# Load_Bank_Mosfet_Control_Board.net
KiCad netlist of a schematic drawn in EAGLE
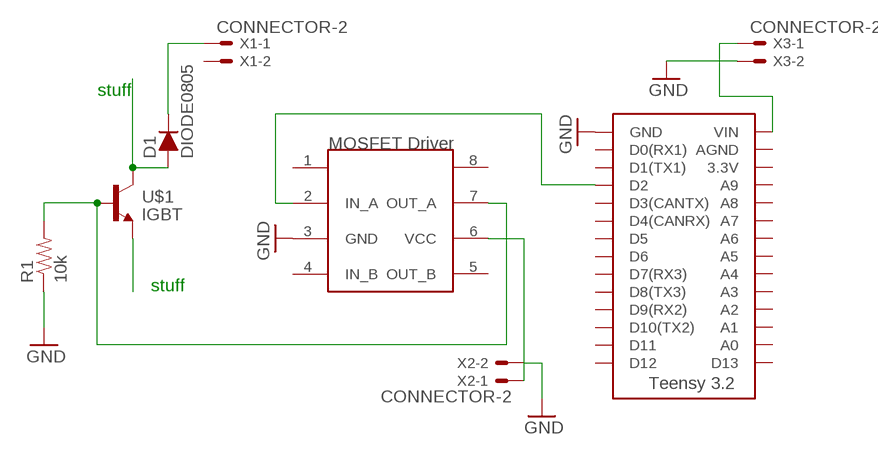
[diagram p0: schematic, sheet 1]

(export (version "E")
  (design (tool "Eeschema 10.0.6"))
  (components
    (comp (ref "D1")
      (value "DIODE0805")
      (footprint "eagle-import:0805_D")
      (libsource (lib "eagle-import") (part "DIODE0805"))
    )
    (comp (ref "R1")
      (value "10k")
      (footprint "eagle-import:0402-RES")
      (libsource (lib "eagle-import") (part "RESISTOR0402"))
    )
    (comp (ref "U$1")
      (value "IGBT")
      (footprint "eagle-import:IGBT")
      (libsource (lib "eagle-import") (part "IGBT"))
    )
    (comp (ref "U$2")
      (value "MC34152")
      (footprint "eagle-import:SOIC-08")
      (libsource (lib "eagle-import") (part "MC34152"))
    )
    (comp (ref "U$3")
      (value "TEENSY_3.2_SIMPLE")
      (footprint "eagle-import:TEENSY_3.2_SIMPLE")
      (libsource (lib "eagle-import") (part "TEENSY_3.2_SIMPLE"))
    )
    (comp (ref "X1")
      (value "CONNECTOR-2")
      (footprint "eagle-import:MINIFIT_5566-2")
      (libsource (lib "eagle-import") (part "CONNECTOR-2"))
    )
    (comp (ref "X2")
      (value "CONNECTOR-2")
      (footprint "eagle-import:MINIFIT_5566-2")
      (libsource (lib "eagle-import") (part "CONNECTOR-2"))
    )
    (comp (ref "X3")
      (value "CONNECTOR-2")
      (footprint "eagle-import:MINIFIT_5566-2")
      (libsource (lib "eagle-import") (part "CONNECTOR-2"))
    )
  )
  (nets
    (net (code "1") (name "GND") (class "Default")
      (node (ref "R1") (pin "1") (pinfunction "1_1") (pintype "passive"))
      (node (ref "U$2") (pin "3") (pinfunction "GND_3") (pintype "power_in"))
      (node (ref "U$3") (pin "GND") (pinfunction "GND_GND") (pintype "bidirectional"))
      (node (ref "X2") (pin "2") (pinfunction "S_2") (pintype "passive"))
      (node (ref "X3") (pin "2") (pinfunction "S_2") (pintype "passive"))
    )
    (net (code "2") (name "Net-(U$1-BASE)") (class "Default")
      (node (ref "R1") (pin "2") (pinfunction "2_2") (pintype "passive"))
      (node (ref "U$1") (pin "P$3") (pinfunction "BASE_P$3") (pintype "passive"))
      (node (ref "U$2") (pin "7") (pinfunction "OUT_A_7") (pintype "output"))
    )
    (net (code "3") (name "Net-(U$1-COLLECTOR)") (class "Default")
      (node (ref "D1") (pin "A") (pinfunction "A_A") (pintype "passive"))
      (node (ref "U$1") (pin "P$2") (pinfunction "COLLECTOR_P$2") (pintype "passive"))
    )
    (net (code "4") (name "Net-(U$1-EMITTER-PadP$1)") (class "Default")
      (node (ref "U$1") (pin "P$1") (pinfunction "EMITTER_P$1") (pintype "passive"))
      (node (ref "U$1") (pin "P$4") (pinfunction "EMITTER_P$4") (pintype "passive"))
    )
    (net (code "5") (name "Net-(U$2-IN_A)") (class "Default")
      (node (ref "U$2") (pin "2") (pinfunction "IN_A_2") (pintype "input"))
      (node (ref "U$3") (pin "D2") (pinfunction "D2_D2") (pintype "bidirectional"))
    )
    (net (code "6") (name "Net-(U$2-VCC)") (class "Default")
      (node (ref "U$2") (pin "6") (pinfunction "VCC_6") (pintype "power_in"))
      (node (ref "X2") (pin "1") (pinfunction "S_1") (pintype "passive"))
    )
    (net (code "7") (name "Net-(X1A-S)") (class "Default")
      (node (ref "D1") (pin "C") (pinfunction "C_C") (pintype "passive"))
      (node (ref "X1") (pin "1") (pinfunction "S_1") (pintype "passive"))
    )
    (net (code "8") (name "Net-(X3A-S)") (class "Default")
      (node (ref "U$3") (pin "VIN") (pinfunction "VIN_VIN") (pintype "bidirectional"))
      (node (ref "X3") (pin "1") (pinfunction "S_1") (pintype "passive"))
    )
    (net (code "9") (name "unconnected-(U$2-IN_B-Pad4)") (class "Default")
      (node (ref "U$2") (pin "4") (pinfunction "IN_B_4") (pintype "bidirectional"))
    )
    (net (code "10") (name "unconnected-(U$2-OUT_B-Pad5)") (class "Default")
      (node (ref "U$2") (pin "5") (pinfunction "OUT_B_5") (pintype "output"))
    )
    (net (code "11") (name "unconnected-(U$2-P$1-Pad1)") (class "Default")
      (node (ref "U$2") (pin "1") (pinfunction "P$1_1") (pintype "tri_state"))
    )
    (net (code "12") (name "unconnected-(U$2-P$5-Pad8)") (class "Default")
      (node (ref "U$2") (pin "8") (pinfunction "P$5_8") (pintype "tri_state"))
    )
    (net (code "13") (name "unconnected-(U$3-Pad3.3V)") (class "Default")
      (node (ref "U$3") (pin "3.3V") (pinfunction "3.3V_3.3V") (pintype "bidirectional"))
    )
    (net (code "14") (name "unconnected-(U$3-PadA0)") (class "Default")
      (node (ref "U$3") (pin "A0") (pinfunction "A0_A0") (pintype "bidirectional"))
    )
    (net (code "15") (name "unconnected-(U$3-PadA1)") (class "Default")
      (node (ref "U$3") (pin "A1") (pinfunction "A1_A1") (pintype "bidirectional"))
    )
    (net (code "16") (name "unconnected-(U$3-PadA2)") (class "Default")
      (node (ref "U$3") (pin "A2") (pinfunction "A2_A2") (pintype "bidirectional"))
    )
    (net (code "17") (name "unconnected-(U$3-PadA3)") (class "Default")
      (node (ref "U$3") (pin "A3") (pinfunction "A3_A3") (pintype "bidirectional"))
    )
    (net (code "18") (name "unconnected-(U$3-PadA4)") (class "Default")
      (node (ref "U$3") (pin "A4") (pinfunction "A4_A4") (pintype "bidirectional"))
    )
    (net (code "19") (name "unconnected-(U$3-PadA5)") (class "Default")
      (node (ref "U$3") (pin "A5") (pinfunction "A5_A5") (pintype "bidirectional"))
    )
    (net (code "20") (name "unconnected-(U$3-PadA6)") (class "Default")
      (node (ref "U$3") (pin "A6") (pinfunction "A6_A6") (pintype "bidirectional"))
    )
    (net (code "21") (name "unconnected-(U$3-PadA7)") (class "Default")
      (node (ref "U$3") (pin "A7") (pinfunction "A7_A7") (pintype "bidirectional"))
    )
    (net (code "22") (name "unconnected-(U$3-PadA8)") (class "Default")
      (node (ref "U$3") (pin "A8") (pinfunction "A8_A8") (pintype "bidirectional"))
    )
    (net (code "23") (name "unconnected-(U$3-PadA9)") (class "Default")
      (node (ref "U$3") (pin "A9") (pinfunction "A9_A9") (pintype "bidirectional"))
    )
    (net (code "24") (name "unconnected-(U$3-PadAGND)") (class "Default")
      (node (ref "U$3") (pin "AGND") (pinfunction "AGND_AGND") (pintype "bidirectional"))
    )
    (net (code "25") (name "unconnected-(U$3-PadD0(RX1))") (class "Default")
      (node (ref "U$3") (pin "D0(RX1)") (pinfunction "D0(RX1)_D0(RX1)") (pintype "bidirectional"))
    )
    (net (code "26") (name "unconnected-(U$3-PadD1(TX1))") (class "Default")
      (node (ref "U$3") (pin "D1(TX1)") (pinfunction "D1(TX1)_D1(TX1)") (pintype "bidirectional"))
    )
    (net (code "27") (name "unconnected-(U$3-PadD3(CANTX))") (class "Default")
      (node (ref "U$3") (pin "D3(CANTX)") (pinfunction "D3(CANTX)_D3(CANTX)") (pintype "bidirectional"))
    )
    (net (code "28") (name "unconnected-(U$3-PadD4(CANRX))") (class "Default")
      (node (ref "U$3") (pin "D4(CANRX)") (pinfunction "D4(CANRX)_D4(CANRX)") (pintype "bidirectional"))
    )
    (net (code "29") (name "unconnected-(U$3-PadD5)") (class "Default")
      (node (ref "U$3") (pin "D5") (pinfunction "D5_D5") (pintype "bidirectional"))
    )
    (net (code "30") (name "unconnected-(U$3-PadD6)") (class "Default")
      (node (ref "U$3") (pin "D6") (pinfunction "D6_D6") (pintype "bidirectional"))
    )
    (net (code "31") (name "unconnected-(U$3-PadD7(RX3))") (class "Default")
      (node (ref "U$3") (pin "D7(RX3)") (pinfunction "D7(RX3)_D7(RX3)") (pintype "bidirectional"))
    )
    (net (code "32") (name "unconnected-(U$3-PadD8(TX3))") (class "Default")
      (node (ref "U$3") (pin "D8(TX3)") (pinfunction "D8(TX3)_D8(TX3)") (pintype "bidirectional"))
    )
    (net (code "33") (name "unconnected-(U$3-PadD9(RX2))") (class "Default")
      (node (ref "U$3") (pin "D9(RX2)") (pinfunction "D9(RX2)_D9(RX2)") (pintype "bidirectional"))
    )
    (net (code "34") (name "unconnected-(U$3-PadD10(TX2))") (class "Default")
      (node (ref "U$3") (pin "D10(TX2)") (pinfunction "D10(TX2)_D10(TX2)") (pintype "bidirectional"))
    )
    (net (code "35") (name "unconnected-(U$3-PadD11)") (class "Default")
      (node (ref "U$3") (pin "D11") (pinfunction "D11_D11") (pintype "bidirectional"))
    )
    (net (code "36") (name "unconnected-(U$3-PadD12)") (class "Default")
      (node (ref "U$3") (pin "D12") (pinfunction "D12_D12") (pintype "bidirectional"))
    )
    (net (code "37") (name "unconnected-(U$3-PadD13)") (class "Default")
      (node (ref "U$3") (pin "D13") (pinfunction "D13_D13") (pintype "bidirectional"))
    )
    (net (code "38") (name "unconnected-(X1B-S-Pad2)") (class "Default")
      (node (ref "X1") (pin "2") (pinfunction "S_2") (pintype "passive"))
    )
  )
)
